# scheme.net
KiCad netlist of a schematic drawn in EAGLE
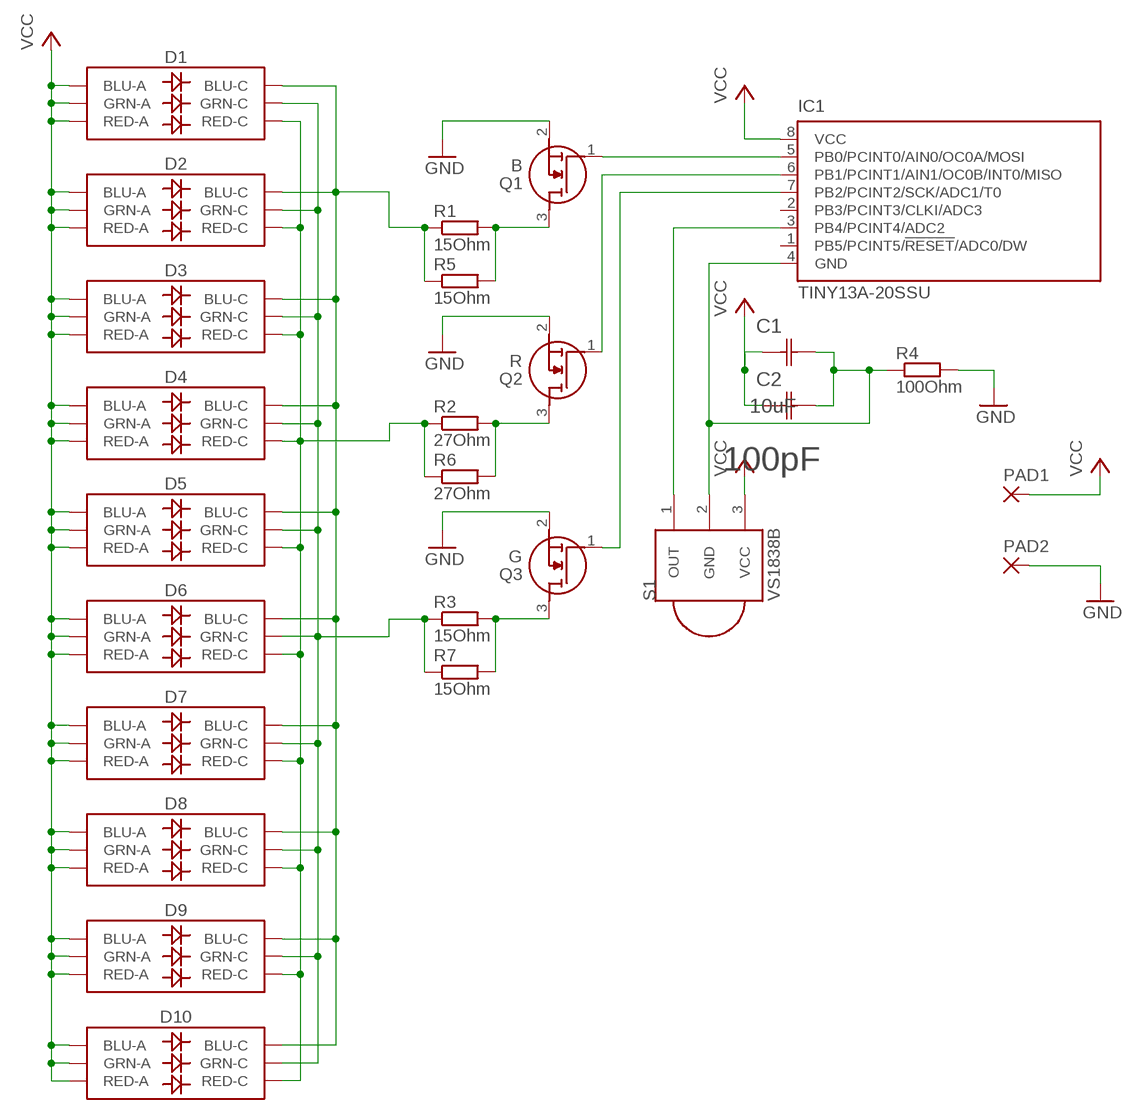
[diagram p0: schematic, sheet 1]

(export (version "E")
  (design (tool "Eeschema 10.0.6"))
  (components
    (comp (ref "C1")
      (value "10uF")
      (footprint "eagle-import:CAPC3216X94N")
      (fields (field (name "MPN") "12061A101JAT2A") (field (name "TOLERANCE") "±5%"))
      (libsource (lib "eagle-import") (part "12061A101JAT2A"))
    )
    (comp (ref "C2")
      (value "100pF")
      (footprint "eagle-import:CAPC2013X94N")
      (fields (field (name "MPN") "08051A100JAT2A") (field (name "TOLERANCE") "±5%"))
      (libsource (lib "eagle-import") (part "08051A100JAT2A"))
    )
    (comp (ref "D1")
      (value "LED-RGBNO_IC")
      (footprint "eagle-import:LED-TRICOLOR-5050")
      (libsource (lib "eagle-import") (part "LED-RGBNO_IC"))
    )
    (comp (ref "D2")
      (value "LED-RGBNO_IC")
      (footprint "eagle-import:LED-TRICOLOR-5050")
      (libsource (lib "eagle-import") (part "LED-RGBNO_IC"))
    )
    (comp (ref "D3")
      (value "LED-RGBNO_IC")
      (footprint "eagle-import:LED-TRICOLOR-5050")
      (libsource (lib "eagle-import") (part "LED-RGBNO_IC"))
    )
    (comp (ref "D4")
      (value "LED-RGBNO_IC")
      (footprint "eagle-import:LED-TRICOLOR-5050")
      (libsource (lib "eagle-import") (part "LED-RGBNO_IC"))
    )
    (comp (ref "D5")
      (value "LED-RGBNO_IC")
      (footprint "eagle-import:LED-TRICOLOR-5050")
      (libsource (lib "eagle-import") (part "LED-RGBNO_IC"))
    )
    (comp (ref "D6")
      (value "LED-RGBNO_IC")
      (footprint "eagle-import:LED-TRICOLOR-5050")
      (libsource (lib "eagle-import") (part "LED-RGBNO_IC"))
    )
    (comp (ref "D7")
      (value "LED-RGBNO_IC")
      (footprint "eagle-import:LED-TRICOLOR-5050")
      (libsource (lib "eagle-import") (part "LED-RGBNO_IC"))
    )
    (comp (ref "D8")
      (value "LED-RGBNO_IC")
      (footprint "eagle-import:LED-TRICOLOR-5050")
      (libsource (lib "eagle-import") (part "LED-RGBNO_IC"))
    )
    (comp (ref "D9")
      (value "LED-RGBNO_IC")
      (footprint "eagle-import:LED-TRICOLOR-5050")
      (libsource (lib "eagle-import") (part "LED-RGBNO_IC"))
    )
    (comp (ref "D10")
      (value "LED-RGBNO_IC")
      (footprint "eagle-import:LED-TRICOLOR-5050")
      (libsource (lib "eagle-import") (part "LED-RGBNO_IC"))
    )
    (comp (ref "IC1")
      (value "TINY13A-20SSU")
      (footprint "eagle-import:8S1")
      (fields (field (name "MPN") "ATTINY13-20SSU"))
      (libsource (lib "eagle-import") (part "TINY13SSU-20"))
    )
    (comp (ref "PAD1")
      (value "SMD2")
      (footprint "eagle-import:SMD1,27-2,54")
      (libsource (lib "eagle-import") (part "SMD2"))
    )
    (comp (ref "PAD2")
      (value "SMD2")
      (footprint "eagle-import:SMD1,27-2,54")
      (libsource (lib "eagle-import") (part "SMD2"))
    )
    (comp (ref "Q1")
      (value "B")
      (footprint "eagle-import:SOT95P280X125-3N")
      (fields (field (name "ARROW_PART_NUMBER") "AO3400"))
      (libsource (lib "eagle-import") (part "AO3400"))
    )
    (comp (ref "Q2")
      (value "R")
      (footprint "eagle-import:SOT95P280X125-3N")
      (fields (field (name "ARROW_PART_NUMBER") "AO3400"))
      (libsource (lib "eagle-import") (part "AO3400"))
    )
    (comp (ref "Q3")
      (value "G")
      (footprint "eagle-import:SOT95P280X125-3N")
      (fields (field (name "ARROW_PART_NUMBER") "AO3400"))
      (libsource (lib "eagle-import") (part "AO3400"))
    )
    (comp (ref "R1")
      (value "15Ohm")
      (footprint "eagle-import:R1206")
      (libsource (lib "eagle-import") (part "R-EU_R1206"))
    )
    (comp (ref "R2")
      (value "27Ohm")
      (footprint "eagle-import:R1206")
      (libsource (lib "eagle-import") (part "R-EU_R1206"))
    )
    (comp (ref "R3")
      (value "15Ohm")
      (footprint "eagle-import:R1206")
      (libsource (lib "eagle-import") (part "R-EU_R1206"))
    )
    (comp (ref "R4")
      (value "100Ohm")
      (footprint "eagle-import:R0805")
      (libsource (lib "eagle-import") (part "R-EU_R0805"))
    )
    (comp (ref "R5")
      (value "15Ohm")
      (footprint "eagle-import:R0805")
      (libsource (lib "eagle-import") (part "R-EU_R0805"))
    )
    (comp (ref "R6")
      (value "27Ohm")
      (footprint "eagle-import:R0805")
      (libsource (lib "eagle-import") (part "R-EU_R0805"))
    )
    (comp (ref "R7")
      (value "15Ohm")
      (footprint "eagle-import:R0805")
      (libsource (lib "eagle-import") (part "R-EU_R0805"))
    )
    (comp (ref "S1")
      (value "VS1838B")
      (footprint "eagle-import:PNA460XM")
      (libsource (lib "eagle-import") (part "PNA460XM"))
    )
  )
  (nets
    (net (code "1") (name "GND") (class "Default")
      (node (ref "PAD2") (pin "1") (pinfunction "P_1") (pintype "passive"))
      (node (ref "Q1") (pin "2") (pinfunction "S_2") (pintype "bidirectional"))
      (node (ref "Q2") (pin "2") (pinfunction "S_2") (pintype "bidirectional"))
      (node (ref "Q3") (pin "2") (pinfunction "S_2") (pintype "bidirectional"))
      (node (ref "R4") (pin "2") (pinfunction "2_2") (pintype "passive"))
    )
    (net (code "2") (name "Net-(C1-C2)") (class "Default")
      (node (ref "C1") (pin "2") (pinfunction "C2_2") (pintype "passive"))
      (node (ref "C2") (pin "2") (pinfunction "C2_2") (pintype "passive"))
      (node (ref "IC1") (pin "4") (pinfunction "GND_4") (pintype "power_in"))
      (node (ref "R4") (pin "1") (pinfunction "1_1") (pintype "passive"))
      (node (ref "S1") (pin "2") (pinfunction "GND_2") (pintype "power_in"))
    )
    (net (code "3") (name "Net-(D1-BLU-C)") (class "Default")
      (node (ref "D1") (pin "6") (pinfunction "BLU-C_6") (pintype "bidirectional"))
      (node (ref "D10") (pin "6") (pinfunction "BLU-C_6") (pintype "bidirectional"))
      (node (ref "D2") (pin "6") (pinfunction "BLU-C_6") (pintype "bidirectional"))
      (node (ref "D3") (pin "6") (pinfunction "BLU-C_6") (pintype "bidirectional"))
      (node (ref "D4") (pin "6") (pinfunction "BLU-C_6") (pintype "bidirectional"))
      (node (ref "D5") (pin "6") (pinfunction "BLU-C_6") (pintype "bidirectional"))
      (node (ref "D6") (pin "6") (pinfunction "BLU-C_6") (pintype "bidirectional"))
      (node (ref "D7") (pin "6") (pinfunction "BLU-C_6") (pintype "bidirectional"))
      (node (ref "D8") (pin "6") (pinfunction "BLU-C_6") (pintype "bidirectional"))
      (node (ref "D9") (pin "6") (pinfunction "BLU-C_6") (pintype "bidirectional"))
      (node (ref "R1") (pin "1") (pinfunction "1_1") (pintype "passive"))
      (node (ref "R5") (pin "1") (pinfunction "1_1") (pintype "passive"))
    )
    (net (code "4") (name "Net-(D1-GRN-C)") (class "Default")
      (node (ref "D1") (pin "4") (pinfunction "GRN-C_4") (pintype "bidirectional"))
      (node (ref "D10") (pin "4") (pinfunction "GRN-C_4") (pintype "bidirectional"))
      (node (ref "D2") (pin "4") (pinfunction "GRN-C_4") (pintype "bidirectional"))
      (node (ref "D3") (pin "4") (pinfunction "GRN-C_4") (pintype "bidirectional"))
      (node (ref "D4") (pin "4") (pinfunction "GRN-C_4") (pintype "bidirectional"))
      (node (ref "D5") (pin "4") (pinfunction "GRN-C_4") (pintype "bidirectional"))
      (node (ref "D6") (pin "4") (pinfunction "GRN-C_4") (pintype "bidirectional"))
      (node (ref "D7") (pin "4") (pinfunction "GRN-C_4") (pintype "bidirectional"))
      (node (ref "D8") (pin "4") (pinfunction "GRN-C_4") (pintype "bidirectional"))
      (node (ref "D9") (pin "4") (pinfunction "GRN-C_4") (pintype "bidirectional"))
      (node (ref "R3") (pin "1") (pinfunction "1_1") (pintype "passive"))
      (node (ref "R7") (pin "1") (pinfunction "1_1") (pintype "passive"))
    )
    (net (code "5") (name "Net-(D1-RED-C)") (class "Default")
      (node (ref "D1") (pin "5") (pinfunction "RED-C_5") (pintype "bidirectional"))
      (node (ref "D10") (pin "5") (pinfunction "RED-C_5") (pintype "bidirectional"))
      (node (ref "D2") (pin "5") (pinfunction "RED-C_5") (pintype "bidirectional"))
      (node (ref "D3") (pin "5") (pinfunction "RED-C_5") (pintype "bidirectional"))
      (node (ref "D4") (pin "5") (pinfunction "RED-C_5") (pintype "bidirectional"))
      (node (ref "D5") (pin "5") (pinfunction "RED-C_5") (pintype "bidirectional"))
      (node (ref "D6") (pin "5") (pinfunction "RED-C_5") (pintype "bidirectional"))
      (node (ref "D7") (pin "5") (pinfunction "RED-C_5") (pintype "bidirectional"))
      (node (ref "D8") (pin "5") (pinfunction "RED-C_5") (pintype "bidirectional"))
      (node (ref "D9") (pin "5") (pinfunction "RED-C_5") (pintype "bidirectional"))
      (node (ref "R2") (pin "1") (pinfunction "1_1") (pintype "passive"))
      (node (ref "R6") (pin "1") (pinfunction "1_1") (pintype "passive"))
    )
    (net (code "6") (name "Net-(IC1-PB0{slash}PCINT0{slash}AIN0{slash}OC0A{slash}MOSI)") (class "Default")
      (node (ref "IC1") (pin "5") (pinfunction "PB0/PCINT0/AIN0/OC0A/MOSI_5") (pintype "bidirectional"))
      (node (ref "Q1") (pin "1") (pinfunction "G_1") (pintype "bidirectional"))
    )
    (net (code "7") (name "Net-(IC1-PB1{slash}PCINT1{slash}AIN1{slash}OC0B{slash}INT0{slash}MISO)") (class "Default")
      (node (ref "IC1") (pin "6") (pinfunction "PB1/PCINT1/AIN1/OC0B/INT0/MISO_6") (pintype "bidirectional"))
      (node (ref "Q2") (pin "1") (pinfunction "G_1") (pintype "bidirectional"))
    )
    (net (code "8") (name "Net-(IC1-PB2{slash}PCINT2{slash}SCK{slash}ADC1{slash}T0)") (class "Default")
      (node (ref "IC1") (pin "7") (pinfunction "PB2/PCINT2/SCK/ADC1/T0_7") (pintype "bidirectional"))
      (node (ref "Q3") (pin "1") (pinfunction "G_1") (pintype "bidirectional"))
    )
    (net (code "9") (name "Net-(IC1-PB4{slash}PCINT4{slash}ADC2)") (class "Default")
      (node (ref "IC1") (pin "3") (pinfunction "PB4/PCINT4/ADC2_3") (pintype "bidirectional"))
      (node (ref "S1") (pin "1") (pinfunction "OUT_1") (pintype "output"))
    )
    (net (code "10") (name "Net-(Q1-D)") (class "Default")
      (node (ref "Q1") (pin "3") (pinfunction "D_3") (pintype "bidirectional"))
      (node (ref "R1") (pin "2") (pinfunction "2_2") (pintype "passive"))
      (node (ref "R5") (pin "2") (pinfunction "2_2") (pintype "passive"))
    )
    (net (code "11") (name "Net-(Q2-D)") (class "Default")
      (node (ref "Q2") (pin "3") (pinfunction "D_3") (pintype "bidirectional"))
      (node (ref "R2") (pin "2") (pinfunction "2_2") (pintype "passive"))
      (node (ref "R6") (pin "2") (pinfunction "2_2") (pintype "passive"))
    )
    (net (code "12") (name "Net-(Q3-D)") (class "Default")
      (node (ref "Q3") (pin "3") (pinfunction "D_3") (pintype "bidirectional"))
      (node (ref "R3") (pin "2") (pinfunction "2_2") (pintype "passive"))
      (node (ref "R7") (pin "2") (pinfunction "2_2") (pintype "passive"))
    )
    (net (code "13") (name "VCC") (class "Default")
      (node (ref "C1") (pin "1") (pinfunction "C1_1") (pintype "passive"))
      (node (ref "C2") (pin "1") (pinfunction "C1_1") (pintype "passive"))
      (node (ref "D1") (pin "1") (pinfunction "BLU-A_1") (pintype "bidirectional"))
      (node (ref "D1") (pin "2") (pinfunction "RED-A_2") (pintype "bidirectional"))
      (node (ref "D1") (pin "3") (pinfunction "GRN-A_3") (pintype "bidirectional"))
      (node (ref "D10") (pin "1") (pinfunction "BLU-A_1") (pintype "bidirectional"))
      (node (ref "D10") (pin "2") (pinfunction "RED-A_2") (pintype "bidirectional"))
      (node (ref "D10") (pin "3") (pinfunction "GRN-A_3") (pintype "bidirectional"))
      (node (ref "D2") (pin "1") (pinfunction "BLU-A_1") (pintype "bidirectional"))
      (node (ref "D2") (pin "2") (pinfunction "RED-A_2") (pintype "bidirectional"))
      (node (ref "D2") (pin "3") (pinfunction "GRN-A_3") (pintype "bidirectional"))
      (node (ref "D3") (pin "1") (pinfunction "BLU-A_1") (pintype "bidirectional"))
      (node (ref "D3") (pin "2") (pinfunction "RED-A_2") (pintype "bidirectional"))
      (node (ref "D3") (pin "3") (pinfunction "GRN-A_3") (pintype "bidirectional"))
      (node (ref "D4") (pin "1") (pinfunction "BLU-A_1") (pintype "bidirectional"))
      (node (ref "D4") (pin "2") (pinfunction "RED-A_2") (pintype "bidirectional"))
      (node (ref "D4") (pin "3") (pinfunction "GRN-A_3") (pintype "bidirectional"))
      (node (ref "D5") (pin "1") (pinfunction "BLU-A_1") (pintype "bidirectional"))
      (node (ref "D5") (pin "2") (pinfunction "RED-A_2") (pintype "bidirectional"))
      (node (ref "D5") (pin "3") (pinfunction "GRN-A_3") (pintype "bidirectional"))
      (node (ref "D6") (pin "1") (pinfunction "BLU-A_1") (pintype "bidirectional"))
      (node (ref "D6") (pin "2") (pinfunction "RED-A_2") (pintype "bidirectional"))
      (node (ref "D6") (pin "3") (pinfunction "GRN-A_3") (pintype "bidirectional"))
      (node (ref "D7") (pin "1") (pinfunction "BLU-A_1") (pintype "bidirectional"))
      (node (ref "D7") (pin "2") (pinfunction "RED-A_2") (pintype "bidirectional"))
      (node (ref "D7") (pin "3") (pinfunction "GRN-A_3") (pintype "bidirectional"))
      (node (ref "D8") (pin "1") (pinfunction "BLU-A_1") (pintype "bidirectional"))
      (node (ref "D8") (pin "2") (pinfunction "RED-A_2") (pintype "bidirectional"))
      (node (ref "D8") (pin "3") (pinfunction "GRN-A_3") (pintype "bidirectional"))
      (node (ref "D9") (pin "1") (pinfunction "BLU-A_1") (pintype "bidirectional"))
      (node (ref "D9") (pin "2") (pinfunction "RED-A_2") (pintype "bidirectional"))
      (node (ref "D9") (pin "3") (pinfunction "GRN-A_3") (pintype "bidirectional"))
      (node (ref "IC1") (pin "8") (pinfunction "VCC_8") (pintype "power_in"))
      (node (ref "PAD1") (pin "1") (pinfunction "P_1") (pintype "passive"))
      (node (ref "S1") (pin "3") (pinfunction "VCC_3") (pintype "power_in"))
    )
    (net (code "14") (name "unconnected-(IC1-PB3{slash}PCINT3{slash}CLKI{slash}ADC3-Pad2)") (class "Default")
      (node (ref "IC1") (pin "2") (pinfunction "PB3/PCINT3/CLKI/ADC3_2") (pintype "bidirectional"))
    )
    (net (code "15") (name "unconnected-(IC1-PB5{slash}PCINT5{slash}~{RESET}{slash}ADC0{slash}DW-Pad1)") (class "Default")
      (node (ref "IC1") (pin "1") (pinfunction "PB5/PCINT5/~{RESET}/ADC0/DW_1") (pintype "bidirectional"))
    )
  )
)
